# Schematic.net
KiCad netlist of a schematic drawn in Altium Designer
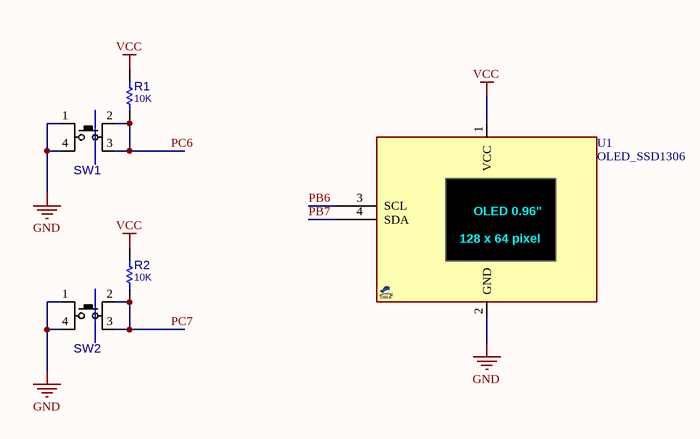
[diagram p0: Schematic.SchDoc]

(export (version "E")
  (design (tool "Eeschema 10.0.6"))
  (components
    (comp (ref "R1")
      (value "10K")
      (footprint "R0402")
      (description "RESISTOR, SMD")
      (libsource (lib "passive_smd") (part "RES_SMD"))
    )
    (comp (ref "R2")
      (value "10K")
      (footprint "R0402")
      (description "RESISTOR, SMD")
      (libsource (lib "passive_smd") (part "RES_SMD"))
    )
    (comp (ref "SW1")
      (value "PUSHBUTTON")
      (footprint "SWPBS_SPDT_3X3TS")
      (description "SWITCH, PUSH BUTTON, TACTILE, SMD, SPDT, 3X3MM")
      (fields (field (name "MANF") "CHINA") (field (name "MANF_P#") "TS-1233"))
      (libsource (lib "switch_tact_PUSHB") (part "SWPBS_SPDT_3X3TS"))
    )
    (comp (ref "SW2")
      (value "PUSHBUTTON")
      (footprint "SWPBS_SPDT_3X3TS")
      (description "SWITCH, PUSH BUTTON, TACTILE, SMD, SPDT, 3X3MM")
      (fields (field (name "MANF") "CHINA") (field (name "MANF_P#") "TS-1233"))
      (libsource (lib "switch_tact_PUSHB") (part "SWPBS_SPDT_3X3TS"))
    )
    (comp (ref "U1")
      (value "OLED_SSD1306")
      (footprint "OLED_SSD1306_64_I2C")
      (description "OLED, SSD1306, 0.96\", 128X64, BREAKOUT I2C")
      (fields (field (name "MANF_P#") "OLED_SSD1306_I2C"))
      (libsource (lib "oled") (part "OLED_SSD1306_64_I2C"))
    )
  )
  (nets
    (net (code "1") (name "/PB6") (class "Default")
      (node (ref "U1") (pin "3") (pinfunction "SCL_3") (pintype "passive"))
    )
    (net (code "2") (name "/PB7") (class "Default")
      (node (ref "U1") (pin "4") (pinfunction "SDA_4") (pintype "passive"))
    )
    (net (code "3") (name "/PC6") (class "Default")
      (node (ref "R1") (pin "1") (pinfunction "1_1") (pintype "passive"))
      (node (ref "SW1") (pin "2") (pinfunction "P3_2") (pintype "passive"))
      (node (ref "SW1") (pin "3") (pinfunction "P4_3") (pintype "passive"))
    )
    (net (code "4") (name "/PC7") (class "Default")
      (node (ref "R2") (pin "1") (pinfunction "1_1") (pintype "passive"))
      (node (ref "SW2") (pin "2") (pinfunction "P3_2") (pintype "passive"))
      (node (ref "SW2") (pin "3") (pinfunction "P4_3") (pintype "passive"))
    )
    (net (code "5") (name "GND") (class "Default")
      (node (ref "SW1") (pin "1") (pinfunction "P1_1") (pintype "passive"))
      (node (ref "SW1") (pin "4") (pinfunction "P2_4") (pintype "passive"))
      (node (ref "SW2") (pin "1") (pinfunction "P1_1") (pintype "passive"))
      (node (ref "SW2") (pin "4") (pinfunction "P2_4") (pintype "passive"))
      (node (ref "U1") (pin "2") (pinfunction "GND_2") (pintype "passive"))
    )
    (net (code "6") (name "VCC") (class "Default")
      (node (ref "R1") (pin "2") (pinfunction "2_2") (pintype "passive"))
      (node (ref "R2") (pin "2") (pinfunction "2_2") (pintype "passive"))
      (node (ref "U1") (pin "1") (pinfunction "VCC_1") (pintype "passive"))
    )
  )
)
